# usb-c-adapter-tester.net
KiCad netlist of a schematic drawn in EAGLE
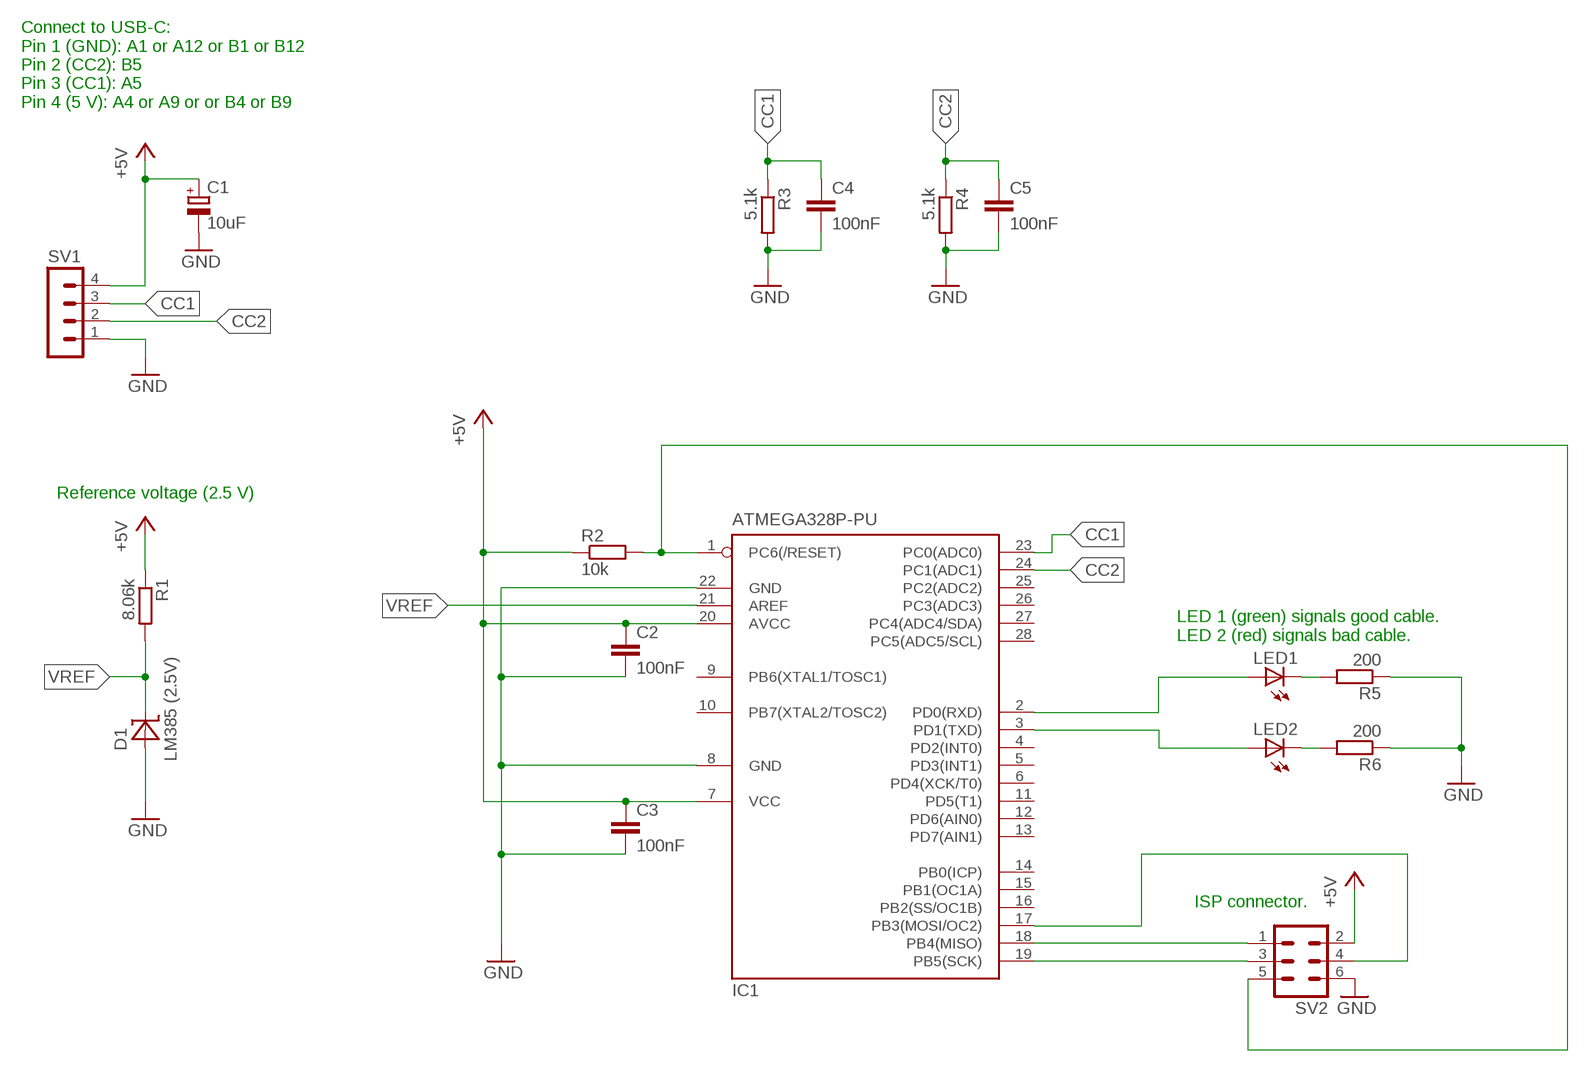
[diagram p0: schematic, sheet 1]

(export (version "E")
  (design (tool "Eeschema 10.0.6"))
  (components
    (comp (ref "C1")
      (value "10uF")
      (footprint "eagle-import:E2,5-5")
      (libsource (lib "eagle-import") (part "CPOL-EUE2.5-5"))
    )
    (comp (ref "C2")
      (value "100nF")
      (footprint "eagle-import:C050-024X044")
      (libsource (lib "eagle-import") (part "C-EU050-024X044"))
    )
    (comp (ref "C3")
      (value "100nF")
      (footprint "eagle-import:C050-024X044")
      (libsource (lib "eagle-import") (part "C-EU050-024X044"))
    )
    (comp (ref "C4")
      (value "100nF")
      (footprint "eagle-import:C050-024X044")
      (libsource (lib "eagle-import") (part "C-EU050-024X044"))
    )
    (comp (ref "C5")
      (value "100nF")
      (footprint "eagle-import:C050-024X044")
      (libsource (lib "eagle-import") (part "C-EU050-024X044"))
    )
    (comp (ref "D1")
      (value "LM385 (2.5V)")
      (footprint "eagle-import:TO-92")
      (libsource (lib "eagle-import") (part "LM385"))
    )
    (comp (ref "IC1")
      (value "ATMEGA328P-PU")
      (footprint "eagle-import:DIL28-3")
      (libsource (lib "eagle-import") (part "MEGA8-P"))
    )
    (comp (ref "LED1")
      (value "LED5MM")
      (footprint "eagle-import:LED5MM")
      (libsource (lib "eagle-import") (part "LED5MM"))
    )
    (comp (ref "LED2")
      (value "LED5MM")
      (footprint "eagle-import:LED5MM")
      (libsource (lib "eagle-import") (part "LED5MM"))
    )
    (comp (ref "R1")
      (value "8.06k")
      (footprint "eagle-import:0207_7")
      (libsource (lib "eagle-import") (part "R-EU_0207/7"))
    )
    (comp (ref "R2")
      (value "10k")
      (footprint "eagle-import:0207_7")
      (libsource (lib "eagle-import") (part "R-EU_0207/7"))
    )
    (comp (ref "R3")
      (value "5.1k")
      (footprint "eagle-import:0207_7")
      (libsource (lib "eagle-import") (part "R-EU_0207/7"))
    )
    (comp (ref "R4")
      (value "5.1k")
      (footprint "eagle-import:0207_7")
      (libsource (lib "eagle-import") (part "R-EU_0207/7"))
    )
    (comp (ref "R5")
      (value "200")
      (footprint "eagle-import:0207_7")
      (libsource (lib "eagle-import") (part "R-EU_0207/7"))
    )
    (comp (ref "R6")
      (value "200")
      (footprint "eagle-import:0207_7")
      (libsource (lib "eagle-import") (part "R-EU_0207/7"))
    )
    (comp (ref "SV1")
      (value "MA04-1")
      (footprint "eagle-import:MA04-1")
      (libsource (lib "eagle-import") (part "MA04-1"))
    )
    (comp (ref "SV2")
      (value "MA03-2")
      (footprint "eagle-import:MA03-2")
      (libsource (lib "eagle-import") (part "MA03-2"))
    )
  )
  (nets
    (net (code "1") (name "+5V") (class "Default")
      (node (ref "C1") (pin "+") (pinfunction "+_+") (pintype "passive"))
      (node (ref "C2") (pin "1") (pinfunction "1_1") (pintype "passive"))
      (node (ref "C3") (pin "1") (pinfunction "1_1") (pintype "passive"))
      (node (ref "IC1") (pin "20") (pinfunction "AVCC_20") (pintype "power_in"))
      (node (ref "IC1") (pin "7") (pinfunction "VCC_7") (pintype "power_in"))
      (node (ref "R1") (pin "1") (pinfunction "1_1") (pintype "passive"))
      (node (ref "R2") (pin "1") (pinfunction "1_1") (pintype "passive"))
      (node (ref "SV1") (pin "4") (pinfunction "4_4") (pintype "passive"))
      (node (ref "SV2") (pin "2") (pinfunction "2_2") (pintype "passive"))
    )
    (net (code "2") (name "CC1") (class "Default")
      (node (ref "C4") (pin "1") (pinfunction "1_1") (pintype "passive"))
      (node (ref "IC1") (pin "23") (pinfunction "PC0(ADC0)_23") (pintype "bidirectional"))
      (node (ref "R3") (pin "1") (pinfunction "1_1") (pintype "passive"))
      (node (ref "SV1") (pin "3") (pinfunction "3_3") (pintype "passive"))
    )
    (net (code "3") (name "CC2") (class "Default")
      (node (ref "C5") (pin "1") (pinfunction "1_1") (pintype "passive"))
      (node (ref "IC1") (pin "24") (pinfunction "PC1(ADC1)_24") (pintype "bidirectional"))
      (node (ref "R4") (pin "1") (pinfunction "1_1") (pintype "passive"))
      (node (ref "SV1") (pin "2") (pinfunction "2_2") (pintype "passive"))
    )
    (net (code "4") (name "GND") (class "Default")
      (node (ref "C1") (pin "-") (pinfunction "-_-") (pintype "passive"))
      (node (ref "C2") (pin "2") (pinfunction "2_2") (pintype "passive"))
      (node (ref "C3") (pin "2") (pinfunction "2_2") (pintype "passive"))
      (node (ref "C4") (pin "2") (pinfunction "2_2") (pintype "passive"))
      (node (ref "C5") (pin "2") (pinfunction "2_2") (pintype "passive"))
      (node (ref "D1") (pin "+") (pinfunction "+_+") (pintype "passive"))
      (node (ref "IC1") (pin "22") (pinfunction "GND_22") (pintype "power_in"))
      (node (ref "IC1") (pin "8") (pinfunction "GND_8") (pintype "power_in"))
      (node (ref "R3") (pin "2") (pinfunction "2_2") (pintype "passive"))
      (node (ref "R4") (pin "2") (pinfunction "2_2") (pintype "passive"))
      (node (ref "R5") (pin "1") (pinfunction "1_1") (pintype "passive"))
      (node (ref "R6") (pin "1") (pinfunction "1_1") (pintype "passive"))
      (node (ref "SV1") (pin "1") (pinfunction "1_1") (pintype "passive"))
      (node (ref "SV2") (pin "6") (pinfunction "6_6") (pintype "passive"))
    )
    (net (code "5") (name "Net-(IC1-PB3(MOSI{slash}OC2))") (class "Default")
      (node (ref "IC1") (pin "17") (pinfunction "PB3(MOSI/OC2)_17") (pintype "bidirectional"))
      (node (ref "SV2") (pin "4") (pinfunction "4_4") (pintype "passive"))
    )
    (net (code "6") (name "Net-(IC1-PB4(MISO))") (class "Default")
      (node (ref "IC1") (pin "18") (pinfunction "PB4(MISO)_18") (pintype "bidirectional"))
      (node (ref "SV2") (pin "1") (pinfunction "1_1") (pintype "passive"))
    )
    (net (code "7") (name "Net-(IC1-PB5(SCK))") (class "Default")
      (node (ref "IC1") (pin "19") (pinfunction "PB5(SCK)_19") (pintype "bidirectional"))
      (node (ref "SV2") (pin "3") (pinfunction "3_3") (pintype "passive"))
    )
    (net (code "8") (name "Net-(IC1-PC6({slash}RESET))") (class "Default")
      (node (ref "IC1") (pin "1") (pinfunction "PC6(/RESET)_1") (pintype "bidirectional"))
      (node (ref "R2") (pin "2") (pinfunction "2_2") (pintype "passive"))
      (node (ref "SV2") (pin "5") (pinfunction "5_5") (pintype "passive"))
    )
    (net (code "9") (name "Net-(IC1-PD0(RXD))") (class "Default")
      (node (ref "IC1") (pin "2") (pinfunction "PD0(RXD)_2") (pintype "bidirectional"))
      (node (ref "LED1") (pin "A") (pinfunction "A_A") (pintype "passive"))
    )
    (net (code "10") (name "Net-(IC1-PD1(TXD))") (class "Default")
      (node (ref "IC1") (pin "3") (pinfunction "PD1(TXD)_3") (pintype "bidirectional"))
      (node (ref "LED2") (pin "A") (pinfunction "A_A") (pintype "passive"))
    )
    (net (code "11") (name "Net-(LED1-C)") (class "Default")
      (node (ref "LED1") (pin "K") (pinfunction "C_K") (pintype "passive"))
      (node (ref "R5") (pin "2") (pinfunction "2_2") (pintype "passive"))
    )
    (net (code "12") (name "Net-(LED2-C)") (class "Default")
      (node (ref "LED2") (pin "K") (pinfunction "C_K") (pintype "passive"))
      (node (ref "R6") (pin "2") (pinfunction "2_2") (pintype "passive"))
    )
    (net (code "13") (name "VREF") (class "Default")
      (node (ref "D1") (pin "-") (pinfunction "-_-") (pintype "passive"))
      (node (ref "IC1") (pin "21") (pinfunction "AREF_21") (pintype "passive"))
      (node (ref "R1") (pin "2") (pinfunction "2_2") (pintype "passive"))
    )
    (net (code "14") (name "unconnected-(IC1-PB0(ICP)-Pad14)") (class "Default")
      (node (ref "IC1") (pin "14") (pinfunction "PB0(ICP)_14") (pintype "bidirectional"))
    )
    (net (code "15") (name "unconnected-(IC1-PB1(OC1A)-Pad15)") (class "Default")
      (node (ref "IC1") (pin "15") (pinfunction "PB1(OC1A)_15") (pintype "bidirectional"))
    )
    (net (code "16") (name "unconnected-(IC1-PB2(SS{slash}OC1B)-Pad16)") (class "Default")
      (node (ref "IC1") (pin "16") (pinfunction "PB2(SS/OC1B)_16") (pintype "bidirectional"))
    )
    (net (code "17") (name "unconnected-(IC1-PB6(XTAL1{slash}TOSC1)-Pad9)") (class "Default")
      (node (ref "IC1") (pin "9") (pinfunction "PB6(XTAL1/TOSC1)_9") (pintype "bidirectional"))
    )
    (net (code "18") (name "unconnected-(IC1-PB7(XTAL2{slash}TOSC2)-Pad10)") (class "Default")
      (node (ref "IC1") (pin "10") (pinfunction "PB7(XTAL2/TOSC2)_10") (pintype "bidirectional"))
    )
    (net (code "19") (name "unconnected-(IC1-PC2(ADC2)-Pad25)") (class "Default")
      (node (ref "IC1") (pin "25") (pinfunction "PC2(ADC2)_25") (pintype "bidirectional"))
    )
    (net (code "20") (name "unconnected-(IC1-PC3(ADC3)-Pad26)") (class "Default")
      (node (ref "IC1") (pin "26") (pinfunction "PC3(ADC3)_26") (pintype "bidirectional"))
    )
    (net (code "21") (name "unconnected-(IC1-PC4(ADC4{slash}SDA)-Pad27)") (class "Default")
      (node (ref "IC1") (pin "27") (pinfunction "PC4(ADC4/SDA)_27") (pintype "bidirectional"))
    )
    (net (code "22") (name "unconnected-(IC1-PC5(ADC5{slash}SCL)-Pad28)") (class "Default")
      (node (ref "IC1") (pin "28") (pinfunction "PC5(ADC5/SCL)_28") (pintype "bidirectional"))
    )
    (net (code "23") (name "unconnected-(IC1-PD2(INT0)-Pad4)") (class "Default")
      (node (ref "IC1") (pin "4") (pinfunction "PD2(INT0)_4") (pintype "bidirectional"))
    )
    (net (code "24") (name "unconnected-(IC1-PD3(INT1)-Pad5)") (class "Default")
      (node (ref "IC1") (pin "5") (pinfunction "PD3(INT1)_5") (pintype "bidirectional"))
    )
    (net (code "25") (name "unconnected-(IC1-PD4(XCK{slash}T0)-Pad6)") (class "Default")
      (node (ref "IC1") (pin "6") (pinfunction "PD4(XCK/T0)_6") (pintype "bidirectional"))
    )
    (net (code "26") (name "unconnected-(IC1-PD5(T1)-Pad11)") (class "Default")
      (node (ref "IC1") (pin "11") (pinfunction "PD5(T1)_11") (pintype "bidirectional"))
    )
    (net (code "27") (name "unconnected-(IC1-PD6(AIN0)-Pad12)") (class "Default")
      (node (ref "IC1") (pin "12") (pinfunction "PD6(AIN0)_12") (pintype "bidirectional"))
    )
    (net (code "28") (name "unconnected-(IC1-PD7(AIN1)-Pad13)") (class "Default")
      (node (ref "IC1") (pin "13") (pinfunction "PD7(AIN1)_13") (pintype "bidirectional"))
    )
  )
)
